# dcmotor.net
KiCad netlist of a schematic drawn in EAGLE
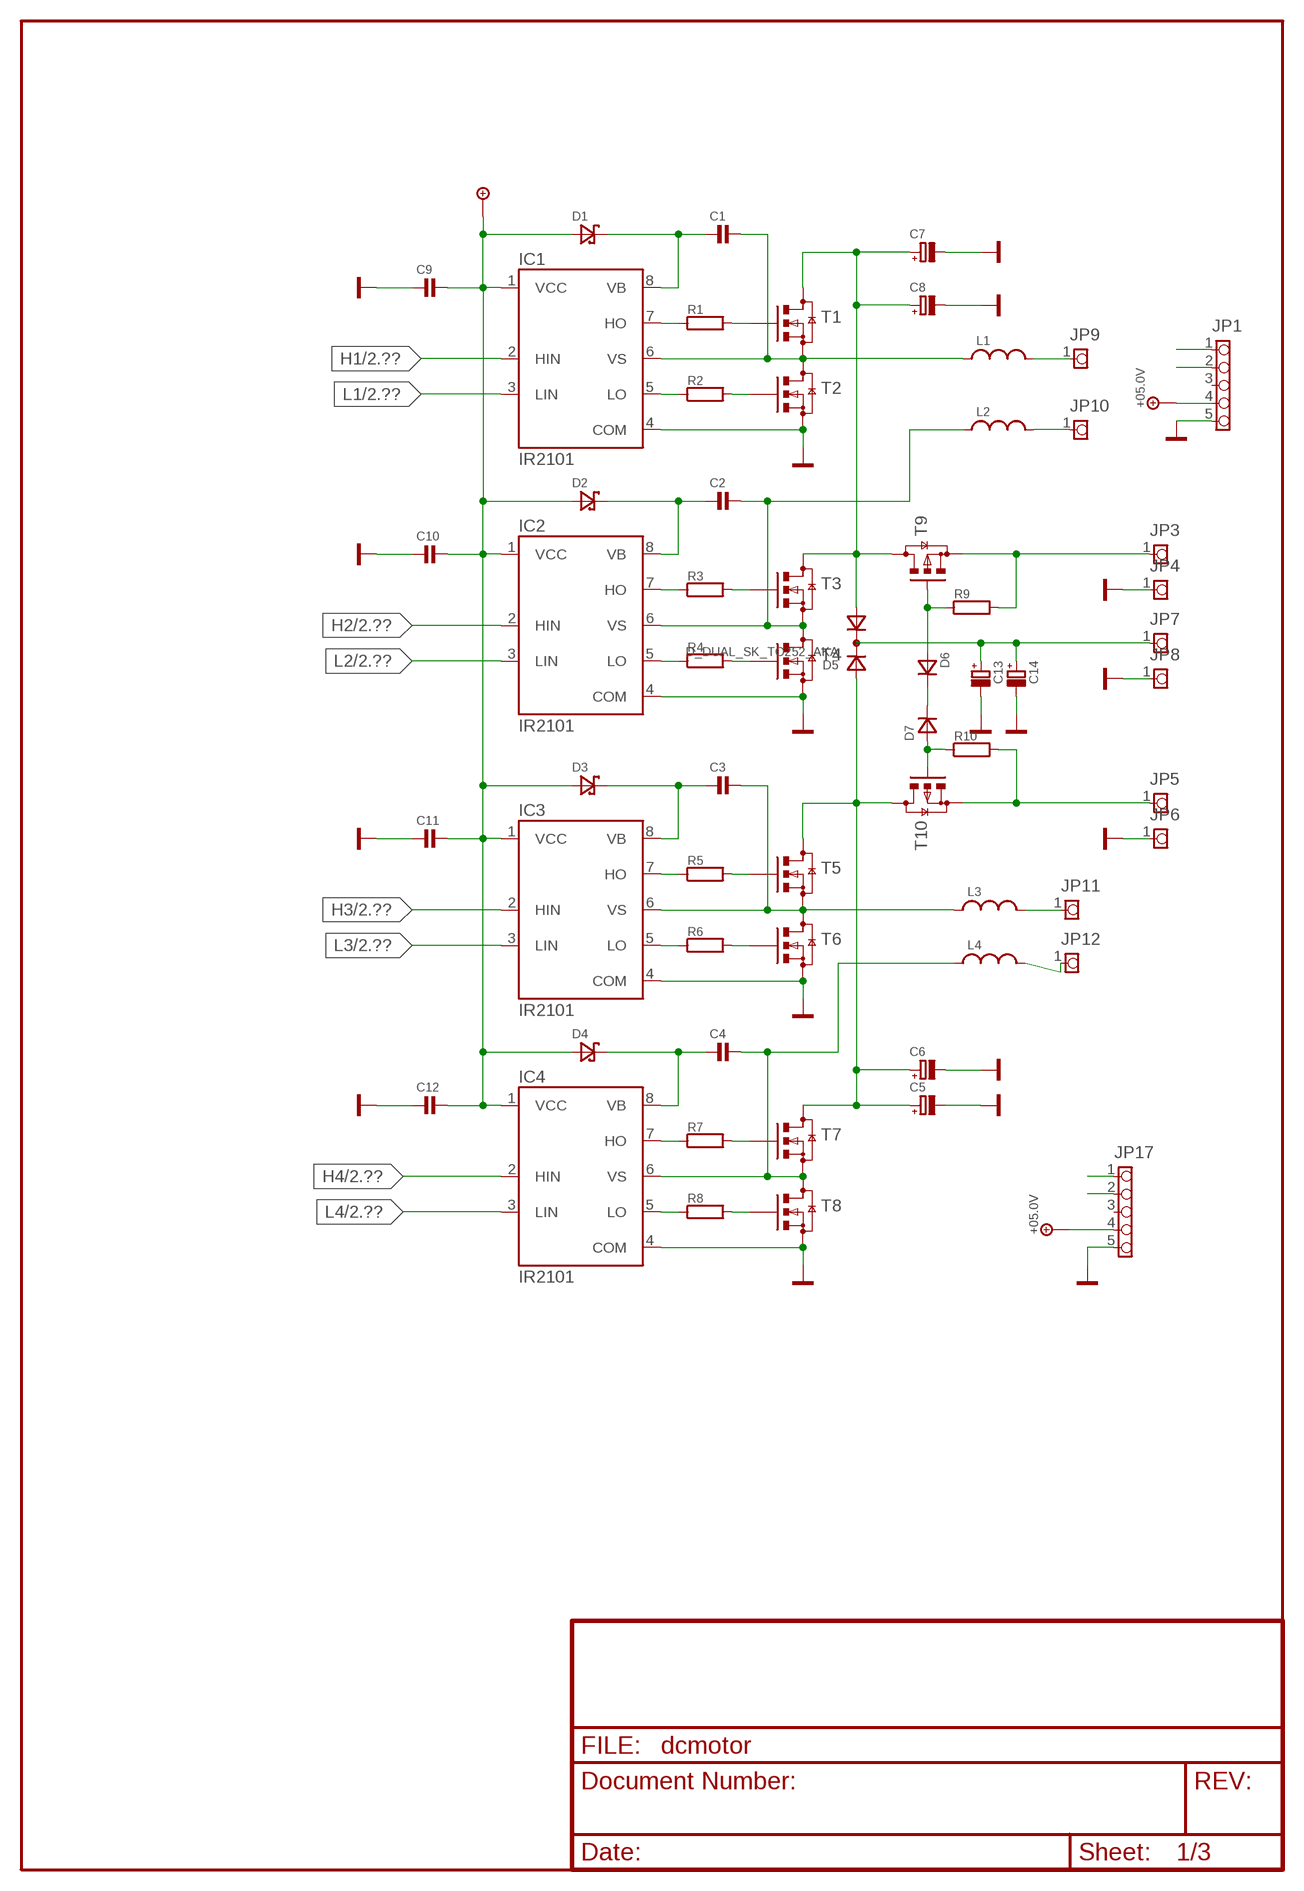
[diagram p0: schematic, sheet 1]
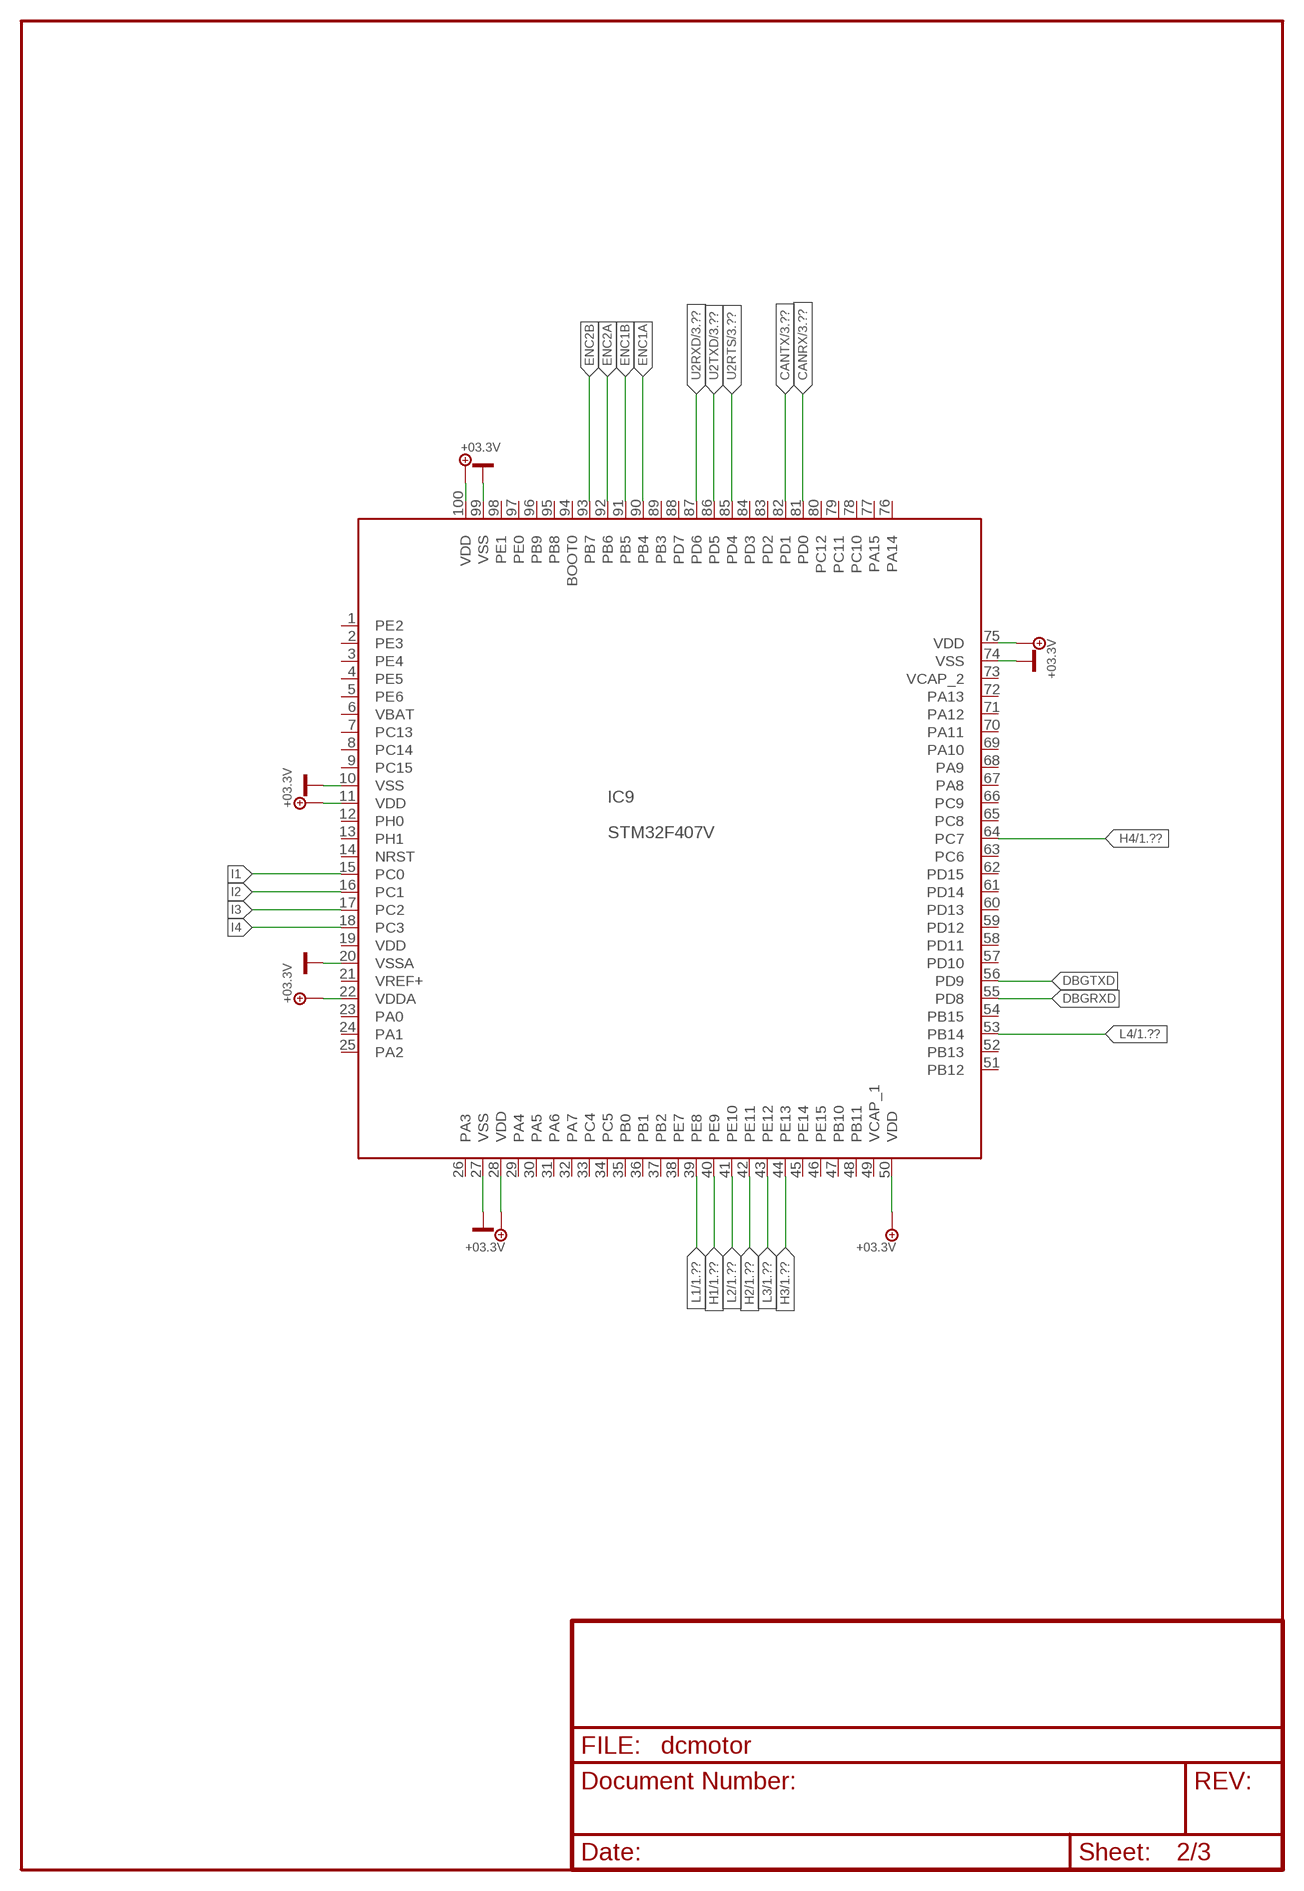
[diagram p1: schematic, sheet 2]
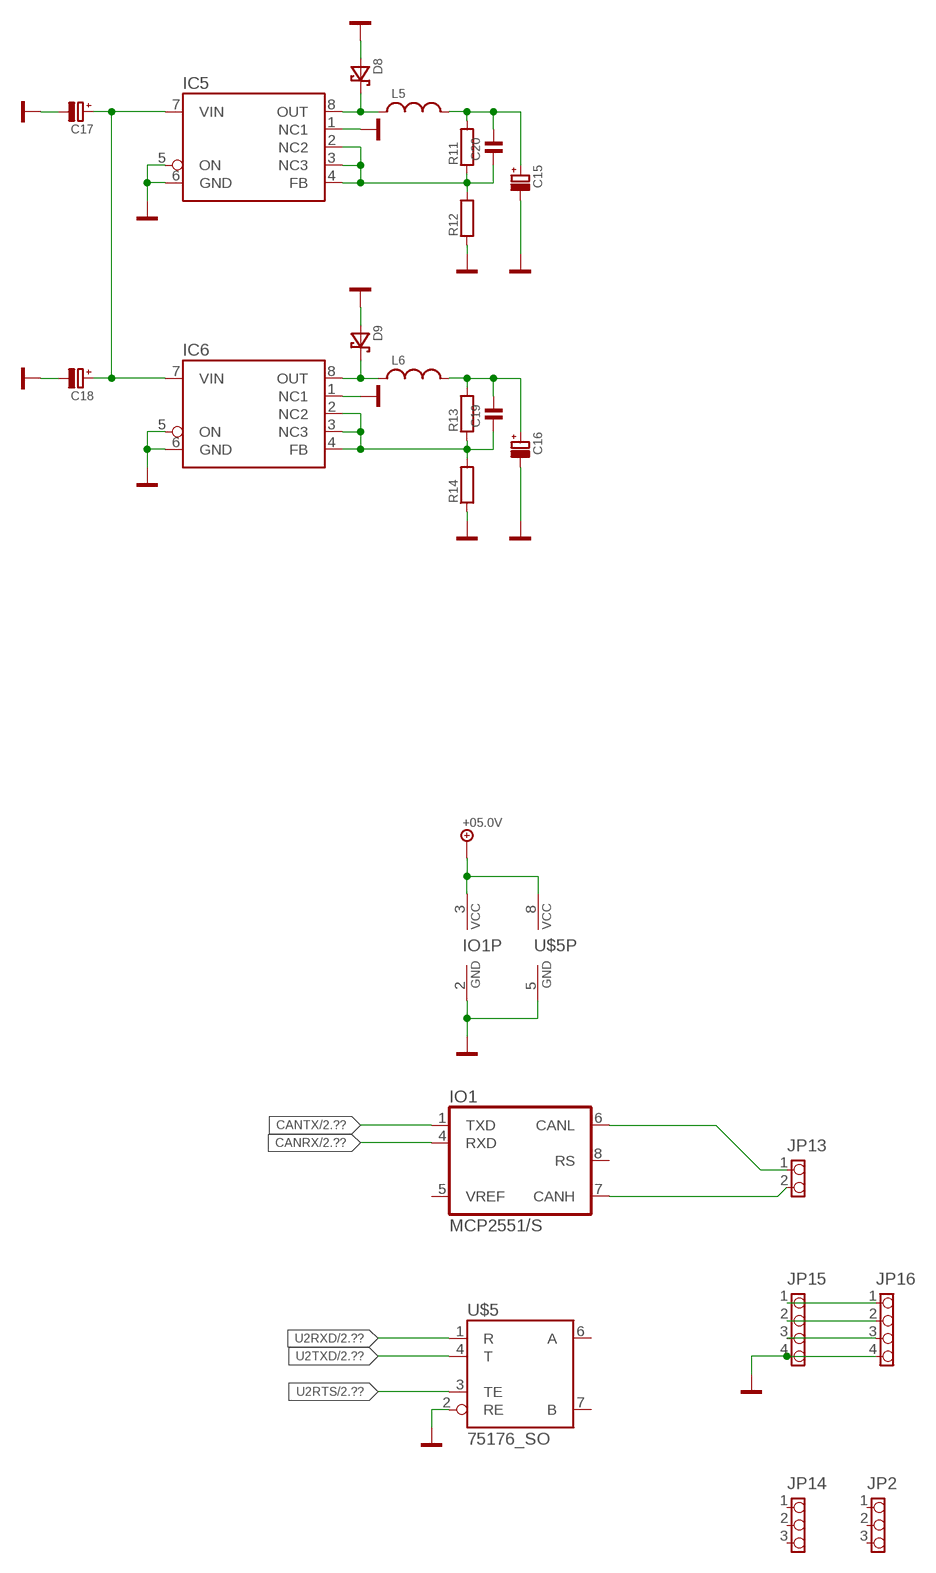
[diagram p2: schematic, sheet 3]

(export (version "E")
  (design (tool "Eeschema 10.0.6"))
  (components
    (comp (ref "C1")
      (value "C1206")
      (footprint "eagle-import:1206")
      (libsource (lib "eagle-import") (part "C1206"))
    )
    (comp (ref "C2")
      (value "C1206")
      (footprint "eagle-import:1206")
      (libsource (lib "eagle-import") (part "C1206"))
    )
    (comp (ref "C3")
      (value "C1206")
      (footprint "eagle-import:1206")
      (libsource (lib "eagle-import") (part "C1206"))
    )
    (comp (ref "C4")
      (value "C1206")
      (footprint "eagle-import:1206")
      (libsource (lib "eagle-import") (part "C1206"))
    )
    (comp (ref "C5")
      (value "CECT7343")
      (footprint "eagle-import:CT7343D")
      (libsource (lib "eagle-import") (part "CECT7343"))
    )
    (comp (ref "C6")
      (value "CECT7343")
      (footprint "eagle-import:CT7343D")
      (libsource (lib "eagle-import") (part "CECT7343"))
    )
    (comp (ref "C7")
      (value "CECT7343")
      (footprint "eagle-import:CT7343D")
      (libsource (lib "eagle-import") (part "CECT7343"))
    )
    (comp (ref "C8")
      (value "CECT7343")
      (footprint "eagle-import:CT7343D")
      (libsource (lib "eagle-import") (part "CECT7343"))
    )
    (comp (ref "C9")
      (value "C1206")
      (footprint "eagle-import:1206")
      (libsource (lib "eagle-import") (part "C1206"))
    )
    (comp (ref "C10")
      (value "C1206")
      (footprint "eagle-import:1206")
      (libsource (lib "eagle-import") (part "C1206"))
    )
    (comp (ref "C11")
      (value "C1206")
      (footprint "eagle-import:1206")
      (libsource (lib "eagle-import") (part "C1206"))
    )
    (comp (ref "C12")
      (value "C1206")
      (footprint "eagle-import:1206")
      (libsource (lib "eagle-import") (part "C1206"))
    )
    (comp (ref "C13")
      (value "CECT7343")
      (footprint "eagle-import:CT7343D")
      (libsource (lib "eagle-import") (part "CECT7343"))
    )
    (comp (ref "C14")
      (value "CECT7343")
      (footprint "eagle-import:CT7343D")
      (libsource (lib "eagle-import") (part "CECT7343"))
    )
    (comp (ref "D1")
      (value "D_SCHOTKY_MLL34")
      (footprint "eagle-import:D_MLL34")
      (libsource (lib "eagle-import") (part "D_SCHOTKY_MLL34"))
    )
    (comp (ref "D2")
      (value "D_SCHOTKY_MLL34")
      (footprint "eagle-import:D_MLL34")
      (libsource (lib "eagle-import") (part "D_SCHOTKY_MLL34"))
    )
    (comp (ref "D3")
      (value "D_SCHOTKY_MLL34")
      (footprint "eagle-import:D_MLL34")
      (libsource (lib "eagle-import") (part "D_SCHOTKY_MLL34"))
    )
    (comp (ref "D4")
      (value "D_SCHOTKY_MLL34")
      (footprint "eagle-import:D_MLL34")
      (libsource (lib "eagle-import") (part "D_SCHOTKY_MLL34"))
    )
    (comp (ref "D5")
      (value "D_DUAL_SK_TO252_AKA")
      (footprint "eagle-import:TO252")
      (libsource (lib "eagle-import") (part "D_DUAL_SK_TO252_AKA"))
    )
    (comp (ref "D6")
      (value "D_MLL34")
      (footprint "eagle-import:D_MLL34")
      (libsource (lib "eagle-import") (part "D_MLL34"))
    )
    (comp (ref "D7")
      (value "D_MLL34")
      (footprint "eagle-import:D_MLL34")
      (libsource (lib "eagle-import") (part "D_MLL34"))
    )
    (comp (ref "IC1")
      (value "IR2101")
      (footprint "eagle-import:SO08")
      (libsource (lib "eagle-import") (part "IR2101"))
    )
    (comp (ref "IC2")
      (value "IR2101")
      (footprint "eagle-import:SO08")
      (libsource (lib "eagle-import") (part "IR2101"))
    )
    (comp (ref "IC3")
      (value "IR2101")
      (footprint "eagle-import:SO08")
      (libsource (lib "eagle-import") (part "IR2101"))
    )
    (comp (ref "IC4")
      (value "IR2101")
      (footprint "eagle-import:SO08")
      (libsource (lib "eagle-import") (part "IR2101"))
    )
    (comp (ref "JP1")
      (value "PINHD-1X5_250_MX5267")
      (footprint "eagle-import:1X05_250_MX5267")
      (libsource (lib "eagle-import") (part "PINHD-1X5_250_MX5267"))
    )
    (comp (ref "JP3")
      (value "PINHD-1X1")
      (footprint "eagle-import:1X01_254")
      (libsource (lib "eagle-import") (part "PINHD-1X1"))
    )
    (comp (ref "JP4")
      (value "PINHD-1X1")
      (footprint "eagle-import:1X01_254")
      (libsource (lib "eagle-import") (part "PINHD-1X1"))
    )
    (comp (ref "JP5")
      (value "PINHD-1X1")
      (footprint "eagle-import:1X01_254")
      (libsource (lib "eagle-import") (part "PINHD-1X1"))
    )
    (comp (ref "JP6")
      (value "PINHD-1X1")
      (footprint "eagle-import:1X01_254")
      (libsource (lib "eagle-import") (part "PINHD-1X1"))
    )
    (comp (ref "JP7")
      (value "PINHD-1X1")
      (footprint "eagle-import:1X01_254")
      (libsource (lib "eagle-import") (part "PINHD-1X1"))
    )
    (comp (ref "JP8")
      (value "PINHD-1X1")
      (footprint "eagle-import:1X01_254")
      (libsource (lib "eagle-import") (part "PINHD-1X1"))
    )
    (comp (ref "JP9")
      (value "PINHD-1X1")
      (footprint "eagle-import:1X01_254")
      (libsource (lib "eagle-import") (part "PINHD-1X1"))
    )
    (comp (ref "JP10")
      (value "PINHD-1X1")
      (footprint "eagle-import:1X01_254")
      (libsource (lib "eagle-import") (part "PINHD-1X1"))
    )
    (comp (ref "JP11")
      (value "PINHD-1X1")
      (footprint "eagle-import:1X01_254")
      (libsource (lib "eagle-import") (part "PINHD-1X1"))
    )
    (comp (ref "JP12")
      (value "PINHD-1X1")
      (footprint "eagle-import:1X01_254")
      (libsource (lib "eagle-import") (part "PINHD-1X1"))
    )
    (comp (ref "JP17")
      (value "PINHD-1X5_250_MX5267")
      (footprint "eagle-import:1X05_250_MX5267")
      (libsource (lib "eagle-import") (part "PINHD-1X5_250_MX5267"))
    )
    (comp (ref "L1")
      (value "L_CDRH127")
      (footprint "eagle-import:L_CDRH127")
      (libsource (lib "eagle-import") (part "L_CDRH127"))
    )
    (comp (ref "L2")
      (value "L_CDRH127")
      (footprint "eagle-import:L_CDRH127")
      (libsource (lib "eagle-import") (part "L_CDRH127"))
    )
    (comp (ref "L3")
      (value "L_CDRH127")
      (footprint "eagle-import:L_CDRH127")
      (libsource (lib "eagle-import") (part "L_CDRH127"))
    )
    (comp (ref "L4")
      (value "L_CDRH127")
      (footprint "eagle-import:L_CDRH127")
      (libsource (lib "eagle-import") (part "L_CDRH127"))
    )
    (comp (ref "R1")
      (value "R_R0603")
      (footprint "eagle-import:0603")
      (libsource (lib "eagle-import") (part "R_R0603"))
    )
    (comp (ref "R2")
      (value "R_R0603")
      (footprint "eagle-import:0603")
      (libsource (lib "eagle-import") (part "R_R0603"))
    )
    (comp (ref "R3")
      (value "R_R0603")
      (footprint "eagle-import:0603")
      (libsource (lib "eagle-import") (part "R_R0603"))
    )
    (comp (ref "R4")
      (value "R_R0603")
      (footprint "eagle-import:0603")
      (libsource (lib "eagle-import") (part "R_R0603"))
    )
    (comp (ref "R5")
      (value "R_R0603")
      (footprint "eagle-import:0603")
      (libsource (lib "eagle-import") (part "R_R0603"))
    )
    (comp (ref "R6")
      (value "R_R0603")
      (footprint "eagle-import:0603")
      (libsource (lib "eagle-import") (part "R_R0603"))
    )
    (comp (ref "R7")
      (value "R_R0603")
      (footprint "eagle-import:0603")
      (libsource (lib "eagle-import") (part "R_R0603"))
    )
    (comp (ref "R8")
      (value "R_R0603")
      (footprint "eagle-import:0603")
      (libsource (lib "eagle-import") (part "R_R0603"))
    )
    (comp (ref "R9")
      (value "R_R0603")
      (footprint "eagle-import:0603")
      (libsource (lib "eagle-import") (part "R_R0603"))
    )
    (comp (ref "R10")
      (value "R_R0603")
      (footprint "eagle-import:0603")
      (libsource (lib "eagle-import") (part "R_R0603"))
    )
    (comp (ref "T1")
      (value "_EMOS_N_TO252_GDS")
      (footprint "eagle-import:TO252")
      (libsource (lib "eagle-import") (part "_EMOS_N_TO252_GDS"))
    )
    (comp (ref "T2")
      (value "_EMOS_N_TO252_GDS")
      (footprint "eagle-import:TO252")
      (libsource (lib "eagle-import") (part "_EMOS_N_TO252_GDS"))
    )
    (comp (ref "T3")
      (value "_EMOS_N_TO252_GDS")
      (footprint "eagle-import:TO252")
      (libsource (lib "eagle-import") (part "_EMOS_N_TO252_GDS"))
    )
    (comp (ref "T4")
      (value "_EMOS_N_TO252_GDS")
      (footprint "eagle-import:TO252")
      (libsource (lib "eagle-import") (part "_EMOS_N_TO252_GDS"))
    )
    (comp (ref "T5")
      (value "_EMOS_N_TO252_GDS")
      (footprint "eagle-import:TO252")
      (libsource (lib "eagle-import") (part "_EMOS_N_TO252_GDS"))
    )
    (comp (ref "T6")
      (value "_EMOS_N_TO252_GDS")
      (footprint "eagle-import:TO252")
      (libsource (lib "eagle-import") (part "_EMOS_N_TO252_GDS"))
    )
    (comp (ref "T7")
      (value "_EMOS_N_TO252_GDS")
      (footprint "eagle-import:TO252")
      (libsource (lib "eagle-import") (part "_EMOS_N_TO252_GDS"))
    )
    (comp (ref "T8")
      (value "_EMOS_N_TO252_GDS")
      (footprint "eagle-import:TO252")
      (libsource (lib "eagle-import") (part "_EMOS_N_TO252_GDS"))
    )
    (comp (ref "T9")
      (value "_EMOS_P_TO252_GDS")
      (footprint "eagle-import:TO252")
      (libsource (lib "eagle-import") (part "_EMOS_P_TO252_GDS"))
    )
    (comp (ref "T10")
      (value "_EMOS_P_TO252_GDS")
      (footprint "eagle-import:TO252")
      (libsource (lib "eagle-import") (part "_EMOS_P_TO252_GDS"))
    )
    (comp (ref "IC9")
      (value "STM32F407V")
      (footprint "eagle-import:LQFP100")
      (libsource (lib "eagle-import") (part "STM32F4V07"))
    )
    (comp (ref "C15")
      (value "CECT7343")
      (footprint "eagle-import:CT7343D")
      (libsource (lib "eagle-import") (part "CECT7343"))
    )
    (comp (ref "C16")
      (value "CECT7343")
      (footprint "eagle-import:CT7343D")
      (libsource (lib "eagle-import") (part "CECT7343"))
    )
    (comp (ref "C17")
      (value "CECT7343")
      (footprint "eagle-import:CT7343D")
      (libsource (lib "eagle-import") (part "CECT7343"))
    )
    (comp (ref "C18")
      (value "CECT7343")
      (footprint "eagle-import:CT7343D")
      (libsource (lib "eagle-import") (part "CECT7343"))
    )
    (comp (ref "C19")
      (value "C0603")
      (footprint "eagle-import:0603")
      (libsource (lib "eagle-import") (part "C0603"))
    )
    (comp (ref "C20")
      (value "C0603")
      (footprint "eagle-import:0603")
      (libsource (lib "eagle-import") (part "C0603"))
    )
    (comp (ref "D8")
      (value "D_SCHOTKY_SMB")
      (footprint "eagle-import:D_SMB")
      (libsource (lib "eagle-import") (part "D_SCHOTKY_SMB"))
    )
    (comp (ref "D9")
      (value "D_SCHOTKY_SMB")
      (footprint "eagle-import:D_SMB")
      (libsource (lib "eagle-import") (part "D_SCHOTKY_SMB"))
    )
    (comp (ref "IC5")
      (value "LM2594_SO")
      (footprint "eagle-import:SO08")
      (libsource (lib "eagle-import") (part "LM2594_SO"))
    )
    (comp (ref "IC6")
      (value "LM2594_SO")
      (footprint "eagle-import:SO08")
      (libsource (lib "eagle-import") (part "LM2594_SO"))
    )
    (comp (ref "IO1")
      (value "MCP2551/S")
      (footprint "eagle-import:SO08")
      (libsource (lib "eagle-import") (part "MCP2551/S"))
    )
    (comp (ref "JP2")
      (value "PINHD-1X3_250_MX5267")
      (footprint "eagle-import:1X03_250_MX5267")
      (libsource (lib "eagle-import") (part "PINHD-1X3_250_MX5267"))
    )
    (comp (ref "JP13")
      (value "PINHD-1X2_250_MX5267")
      (footprint "eagle-import:1X02_250_MX5267")
      (libsource (lib "eagle-import") (part "PINHD-1X2_250_MX5267"))
    )
    (comp (ref "JP14")
      (value "PINHD-1X3_250_MX5267")
      (footprint "eagle-import:1X03_250_MX5267")
      (libsource (lib "eagle-import") (part "PINHD-1X3_250_MX5267"))
    )
    (comp (ref "JP15")
      (value "PINHD-1X4_250_MX5267")
      (footprint "eagle-import:1X04_250_MX5267")
      (libsource (lib "eagle-import") (part "PINHD-1X4_250_MX5267"))
    )
    (comp (ref "JP16")
      (value "PINHD-1X4_250_MX5267")
      (footprint "eagle-import:1X04_250_MX5267")
      (libsource (lib "eagle-import") (part "PINHD-1X4_250_MX5267"))
    )
    (comp (ref "L5")
      (value "L_SMD_350_200")
      (footprint "eagle-import:L_350_200")
      (libsource (lib "eagle-import") (part "L_SMD_350_200"))
    )
    (comp (ref "L6")
      (value "L_SMD_350_200")
      (footprint "eagle-import:L_350_200")
      (libsource (lib "eagle-import") (part "L_SMD_350_200"))
    )
    (comp (ref "R11")
      (value "R_R0603")
      (footprint "eagle-import:0603")
      (libsource (lib "eagle-import") (part "R_R0603"))
    )
    (comp (ref "R12")
      (value "R_R0603")
      (footprint "eagle-import:0603")
      (libsource (lib "eagle-import") (part "R_R0603"))
    )
    (comp (ref "R13")
      (value "R_R0603")
      (footprint "eagle-import:0603")
      (libsource (lib "eagle-import") (part "R_R0603"))
    )
    (comp (ref "R14")
      (value "R_R0603")
      (footprint "eagle-import:0603")
      (libsource (lib "eagle-import") (part "R_R0603"))
    )
    (comp (ref "U$5")
      (value "75176_SO")
      (footprint "eagle-import:SO08")
      (libsource (lib "eagle-import") (part "75176_SO"))
    )
  )
  (nets
    (net (code "1") (name "+3.3V") (class "Default")
      (node (ref "IC9") (pin "100") (pinfunction "VDD_100") (pintype "passive"))
      (node (ref "IC9") (pin "11") (pinfunction "VDD_11") (pintype "passive"))
      (node (ref "IC9") (pin "22") (pinfunction "VDDA_22") (pintype "passive"))
      (node (ref "IC9") (pin "28") (pinfunction "VDD_28") (pintype "passive"))
      (node (ref "IC9") (pin "50") (pinfunction "VDD_50") (pintype "passive"))
      (node (ref "IC9") (pin "75") (pinfunction "VDD_75") (pintype "passive"))
    )
    (net (code "2") (name "+5.0V") (class "Default")
      (node (ref "IO1") (pin "3") (pinfunction "VCC_3") (pintype "power_in"))
      (node (ref "JP1") (pin "4") (pinfunction "4_4") (pintype "passive"))
      (node (ref "JP17") (pin "4") (pinfunction "4_4") (pintype "passive"))
      (node (ref "U$5") (pin "8") (pinfunction "VCC_8") (pintype "power_in"))
    )
    (net (code "3") (name "+15V") (class "Default")
      (node (ref "C10") (pin "1") (pinfunction "1_1") (pintype "passive"))
      (node (ref "C11") (pin "1") (pinfunction "1_1") (pintype "passive"))
      (node (ref "C12") (pin "1") (pinfunction "1_1") (pintype "passive"))
      (node (ref "C9") (pin "1") (pinfunction "1_1") (pintype "passive"))
      (node (ref "D1") (pin "A") (pinfunction "A_A") (pintype "passive"))
      (node (ref "D2") (pin "A") (pinfunction "A_A") (pintype "passive"))
      (node (ref "D3") (pin "A") (pinfunction "A_A") (pintype "passive"))
      (node (ref "D4") (pin "A") (pinfunction "A_A") (pintype "passive"))
      (node (ref "IC1") (pin "1") (pinfunction "VCC_1") (pintype "passive"))
      (node (ref "IC2") (pin "1") (pinfunction "VCC_1") (pintype "passive"))
      (node (ref "IC3") (pin "1") (pinfunction "VCC_1") (pintype "passive"))
      (node (ref "IC4") (pin "1") (pinfunction "VCC_1") (pintype "passive"))
    )
    (net (code "4") (name "CANRX") (class "Default")
      (node (ref "IC9") (pin "81") (pinfunction "PD0_81") (pintype "passive"))
      (node (ref "IO1") (pin "4") (pinfunction "RXD_4") (pintype "output"))
    )
    (net (code "5") (name "CANTX") (class "Default")
      (node (ref "IC9") (pin "82") (pinfunction "PD1_82") (pintype "passive"))
      (node (ref "IO1") (pin "1") (pinfunction "TXD_1") (pintype "input"))
    )
    (net (code "6") (name "DBGRXD") (class "Default")
      (node (ref "IC9") (pin "55") (pinfunction "PD8_55") (pintype "passive"))
    )
    (net (code "7") (name "DBGTXD") (class "Default")
      (node (ref "IC9") (pin "56") (pinfunction "PD9_56") (pintype "passive"))
    )
    (net (code "8") (name "ENC1A") (class "Default")
      (node (ref "IC9") (pin "90") (pinfunction "PB4_90") (pintype "passive"))
      (node (ref "JP1") (pin "1") (pinfunction "1_1") (pintype "passive"))
    )
    (net (code "9") (name "ENC1B") (class "Default")
      (node (ref "IC9") (pin "91") (pinfunction "PB5_91") (pintype "passive"))
      (node (ref "JP1") (pin "2") (pinfunction "2_2") (pintype "passive"))
    )
    (net (code "10") (name "ENC2A") (class "Default")
      (node (ref "IC9") (pin "92") (pinfunction "PB6_92") (pintype "passive"))
      (node (ref "JP17") (pin "1") (pinfunction "1_1") (pintype "passive"))
    )
    (net (code "11") (name "ENC2B") (class "Default")
      (node (ref "IC9") (pin "93") (pinfunction "PB7_93") (pintype "passive"))
      (node (ref "JP17") (pin "2") (pinfunction "2_2") (pintype "passive"))
    )
    (net (code "12") (name "GND") (class "Default")
      (node (ref "C10") (pin "2") (pinfunction "2_2") (pintype "passive"))
      (node (ref "C11") (pin "2") (pinfunction "2_2") (pintype "passive"))
      (node (ref "C12") (pin "2") (pinfunction "2_2") (pintype "passive"))
      (node (ref "C13") (pin "-") (pinfunction "-_-") (pintype "passive"))
      (node (ref "C14") (pin "-") (pinfunction "-_-") (pintype "passive"))
      (node (ref "C15") (pin "-") (pinfunction "-_-") (pintype "passive"))
      (node (ref "C16") (pin "-") (pinfunction "-_-") (pintype "passive"))
      (node (ref "C17") (pin "-") (pinfunction "-_-") (pintype "passive"))
      (node (ref "C18") (pin "-") (pinfunction "-_-") (pintype "passive"))
      (node (ref "C5") (pin "-") (pinfunction "-_-") (pintype "passive"))
      (node (ref "C6") (pin "-") (pinfunction "-_-") (pintype "passive"))
      (node (ref "C7") (pin "-") (pinfunction "-_-") (pintype "passive"))
      (node (ref "C8") (pin "-") (pinfunction "-_-") (pintype "passive"))
      (node (ref "C9") (pin "2") (pinfunction "2_2") (pintype "passive"))
      (node (ref "D8") (pin "A") (pinfunction "A_A") (pintype "passive"))
      (node (ref "D9") (pin "A") (pinfunction "A_A") (pintype "passive"))
      (node (ref "IC1") (pin "4") (pinfunction "COM_4") (pintype "passive"))
      (node (ref "IC2") (pin "4") (pinfunction "COM_4") (pintype "passive"))
      (node (ref "IC3") (pin "4") (pinfunction "COM_4") (pintype "passive"))
      (node (ref "IC4") (pin "4") (pinfunction "COM_4") (pintype "passive"))
      (node (ref "IC5") (pin "1") (pinfunction "NC1_1") (pintype "passive"))
      (node (ref "IC5") (pin "5") (pinfunction "ON_5") (pintype "passive"))
      (node (ref "IC5") (pin "6") (pinfunction "GND_6") (pintype "passive"))
      (node (ref "IC6") (pin "1") (pinfunction "NC1_1") (pintype "passive"))
      (node (ref "IC6") (pin "5") (pinfunction "ON_5") (pintype "passive"))
      (node (ref "IC6") (pin "6") (pinfunction "GND_6") (pintype "passive"))
      (node (ref "IC9") (pin "10") (pinfunction "VSS_10") (pintype "passive"))
      (node (ref "IC9") (pin "20") (pinfunction "VSSA_20") (pintype "passive"))
      (node (ref "IC9") (pin "27") (pinfunction "VSS_27") (pintype "passive"))
      (node (ref "IC9") (pin "74") (pinfunction "VSS_74") (pintype "passive"))
      (node (ref "IC9") (pin "99") (pinfunction "VSS_99") (pintype "passive"))
      (node (ref "IO1") (pin "2") (pinfunction "GND_2") (pintype "power_in"))
      (node (ref "JP1") (pin "5") (pinfunction "5_5") (pintype "passive"))
      (node (ref "JP15") (pin "4") (pinfunction "4_4") (pintype "passive"))
      (node (ref "JP16") (pin "4") (pinfunction "4_4") (pintype "passive"))
      (node (ref "JP17") (pin "5") (pinfunction "5_5") (pintype "passive"))
      (node (ref "JP4") (pin "1") (pinfunction "1_1") (pintype "passive"))
      (node (ref "JP6") (pin "1") (pinfunction "1_1") (pintype "passive"))
      (node (ref "JP8") (pin "1") (pinfunction "1_1") (pintype "passive"))
      (node (ref "R12") (pin "1") (pinfunction "1_1") (pintype "passive"))
      (node (ref "R14") (pin "1") (pinfunction "1_1") (pintype "passive"))
      (node (ref "T2") (pin "3") (pinfunction "S_3") (pintype "passive"))
      (node (ref "T4") (pin "3") (pinfunction "S_3") (pintype "passive"))
      (node (ref "T6") (pin "3") (pinfunction "S_3") (pintype "passive"))
      (node (ref "T8") (pin "3") (pinfunction "S_3") (pintype "passive"))
      (node (ref "U$5") (pin "2") (pinfunction "RE_2") (pintype "input"))
      (node (ref "U$5") (pin "5") (pinfunction "GND_5") (pintype "power_in"))
    )
    (net (code "13") (name "H1") (class "Default")
      (node (ref "IC1") (pin "2") (pinfunction "HIN_2") (pintype "passive"))
      (node (ref "IC9") (pin "40") (pinfunction "PE9_40") (pintype "passive"))
    )
    (net (code "14") (name "H2") (class "Default")
      (node (ref "IC2") (pin "2") (pinfunction "HIN_2") (pintype "passive"))
      (node (ref "IC9") (pin "42") (pinfunction "PE11_42") (pintype "passive"))
    )
    (net (code "15") (name "H3") (class "Default")
      (node (ref "IC3") (pin "2") (pinfunction "HIN_2") (pintype "passive"))
      (node (ref "IC9") (pin "44") (pinfunction "PE13_44") (pintype "passive"))
    )
    (net (code "16") (name "H4") (class "Default")
      (node (ref "IC4") (pin "2") (pinfunction "HIN_2") (pintype "passive"))
      (node (ref "IC9") (pin "64") (pinfunction "PC7_64") (pintype "passive"))
    )
    (net (code "17") (name "I1") (class "Default")
      (node (ref "IC9") (pin "15") (pinfunction "PC0_15") (pintype "passive"))
    )
    (net (code "18") (name "I2") (class "Default")
      (node (ref "IC9") (pin "16") (pinfunction "PC1_16") (pintype "passive"))
    )
    (net (code "19") (name "I3") (class "Default")
      (node (ref "IC9") (pin "17") (pinfunction "PC2_17") (pintype "passive"))
    )
    (net (code "20") (name "I4") (class "Default")
      (node (ref "IC9") (pin "18") (pinfunction "PC3_18") (pintype "passive"))
    )
    (net (code "21") (name "L1") (class "Default")
      (node (ref "IC1") (pin "3") (pinfunction "LIN_3") (pintype "passive"))
      (node (ref "IC9") (pin "39") (pinfunction "PE8_39") (pintype "passive"))
    )
    (net (code "22") (name "L2") (class "Default")
      (node (ref "IC2") (pin "3") (pinfunction "LIN_3") (pintype "passive"))
      (node (ref "IC9") (pin "41") (pinfunction "PE10_41") (pintype "passive"))
    )
    (net (code "23") (name "L3") (class "Default")
      (node (ref "IC3") (pin "3") (pinfunction "LIN_3") (pintype "passive"))
      (node (ref "IC9") (pin "43") (pinfunction "PE12_43") (pintype "passive"))
    )
    (net (code "24") (name "L4") (class "Default")
      (node (ref "IC4") (pin "3") (pinfunction "LIN_3") (pintype "passive"))
      (node (ref "IC9") (pin "53") (pinfunction "PB14_53") (pintype "passive"))
    )
    (net (code "25") (name "Net-(C15-Pad+)") (class "Default")
      (node (ref "C15") (pin "+") (pinfunction "+_+") (pintype "passive"))
      (node (ref "C20") (pin "1") (pinfunction "1_1") (pintype "passive"))
      (node (ref "L5") (pin "1") (pinfunction "1_1") (pintype "passive"))
      (node (ref "R11") (pin "2") (pinfunction "2_2") (pintype "passive"))
    )
    (net (code "26") (name "Net-(C16-Pad+)") (class "Default")
      (node (ref "C16") (pin "+") (pinfunction "+_+") (pintype "passive"))
      (node (ref "C19") (pin "1") (pinfunction "1_1") (pintype "passive"))
      (node (ref "L6") (pin "1") (pinfunction "1_1") (pintype "passive"))
      (node (ref "R13") (pin "2") (pinfunction "2_2") (pintype "passive"))
    )
    (net (code "27") (name "Net-(D5-A1)") (class "Default")
      (node (ref "C7") (pin "+") (pinfunction "+_+") (pintype "passive"))
      (node (ref "C8") (pin "+") (pinfunction "+_+") (pintype "passive"))
      (node (ref "D5") (pin "1") (pinfunction "A1_1") (pintype "passive"))
      (node (ref "T1") (pin "2") (pinfunction "D_2") (pintype "passive"))
      (node (ref "T3") (pin "2") (pinfunction "D_2") (pintype "passive"))
      (node (ref "T9") (pin "2") (pinfunction "D_2") (pintype "passive"))
    )
    (net (code "28") (name "Net-(D5-A2)") (class "Default")
      (node (ref "C5") (pin "+") (pinfunction "+_+") (pintype "passive"))
      (node (ref "C6") (pin "+") (pinfunction "+_+") (pintype "passive"))
      (node (ref "D5") (pin "3") (pinfunction "A2_3") (pintype "passive"))
      (node (ref "T10") (pin "2") (pinfunction "D_2") (pintype "passive"))
      (node (ref "T5") (pin "2") (pinfunction "D_2") (pintype "passive"))
      (node (ref "T7") (pin "2") (pinfunction "D_2") (pintype "passive"))
    )
    (net (code "29") (name "Net-(D5-K)") (class "Default")
      (node (ref "C13") (pin "+") (pinfunction "+_+") (pintype "passive"))
      (node (ref "C14") (pin "+") (pinfunction "+_+") (pintype "passive"))
      (node (ref "D5") (pin "2") (pinfunction "K_2") (pintype "passive"))
      (node (ref "JP7") (pin "1") (pinfunction "1_1") (pintype "passive"))
    )
    (net (code "30") (name "Net-(D6-PadK)") (class "Default")
      (node (ref "D6") (pin "K") (pinfunction "K_K") (pintype "passive"))
      (node (ref "D7") (pin "K") (pinfunction "K_K") (pintype "passive"))
    )
    (net (code "31") (name "Net-(IC1-HO)") (class "Default")
      (node (ref "IC1") (pin "7") (pinfunction "HO_7") (pintype "passive"))
      (node (ref "R1") (pin "1") (pinfunction "1_1") (pintype "passive"))
    )
    (net (code "32") (name "Net-(IC1-LO)") (class "Default")
      (node (ref "IC1") (pin "5") (pinfunction "LO_5") (pintype "passive"))
      (node (ref "R2") (pin "1") (pinfunction "1_1") (pintype "passive"))
    )
    (net (code "33") (name "Net-(IC1-VB)") (class "Default")
      (node (ref "C1") (pin "2") (pinfunction "2_2") (pintype "passive"))
      (node (ref "D1") (pin "K") (pinfunction "K_K") (pintype "passive"))
      (node (ref "IC1") (pin "8") (pinfunction "VB_8") (pintype "passive"))
    )
    (net (code "34") (name "Net-(IC1-VS)") (class "Default")
      (node (ref "C1") (pin "1") (pinfunction "1_1") (pintype "passive"))
      (node (ref "IC1") (pin "6") (pinfunction "VS_6") (pintype "passive"))
      (node (ref "L1") (pin "2") (pinfunction "2_2") (pintype "passive"))
      (node (ref "T1") (pin "3") (pinfunction "S_3") (pintype "passive"))
      (node (ref "T2") (pin "2") (pinfunction "D_2") (pintype "passive"))
    )
    (net (code "35") (name "Net-(IC2-HO)") (class "Default")
      (node (ref "IC2") (pin "7") (pinfunction "HO_7") (pintype "passive"))
      (node (ref "R3") (pin "1") (pinfunction "1_1") (pintype "passive"))
    )
    (net (code "36") (name "Net-(IC2-LO)") (class "Default")
      (node (ref "IC2") (pin "5") (pinfunction "LO_5") (pintype "passive"))
      (node (ref "R4") (pin "1") (pinfunction "1_1") (pintype "passive"))
    )
    (net (code "37") (name "Net-(IC2-VB)") (class "Default")
      (node (ref "C2") (pin "2") (pinfunction "2_2") (pintype "passive"))
      (node (ref "D2") (pin "K") (pinfunction "K_K") (pintype "passive"))
      (node (ref "IC2") (pin "8") (pinfunction "VB_8") (pintype "passive"))
    )
    (net (code "38") (name "Net-(IC2-VS)") (class "Default")
      (node (ref "C2") (pin "1") (pinfunction "1_1") (pintype "passive"))
      (node (ref "IC2") (pin "6") (pinfunction "VS_6") (pintype "passive"))
      (node (ref "L2") (pin "2") (pinfunction "2_2") (pintype "passive"))
      (node (ref "T3") (pin "3") (pinfunction "S_3") (pintype "passive"))
      (node (ref "T4") (pin "2") (pinfunction "D_2") (pintype "passive"))
    )
    (net (code "39") (name "Net-(IC3-HO)") (class "Default")
      (node (ref "IC3") (pin "7") (pinfunction "HO_7") (pintype "passive"))
      (node (ref "R5") (pin "1") (pinfunction "1_1") (pintype "passive"))
    )
    (net (code "40") (name "Net-(IC3-LO)") (class "Default")
      (node (ref "IC3") (pin "5") (pinfunction "LO_5") (pintype "passive"))
      (node (ref "R6") (pin "1") (pinfunction "1_1") (pintype "passive"))
    )
    (net (code "41") (name "Net-(IC3-VB)") (class "Default")
      (node (ref "C3") (pin "2") (pinfunction "2_2") (pintype "passive"))
      (node (ref "D3") (pin "K") (pinfunction "K_K") (pintype "passive"))
      (node (ref "IC3") (pin "8") (pinfunction "VB_8") (pintype "passive"))
    )
    (net (code "42") (name "Net-(IC3-VS)") (class "Default")
      (node (ref "C3") (pin "1") (pinfunction "1_1") (pintype "passive"))
      (node (ref "IC3") (pin "6") (pinfunction "VS_6") (pintype "passive"))
      (node (ref "L3") (pin "2") (pinfunction "2_2") (pintype "passive"))
      (node (ref "T5") (pin "3") (pinfunction "S_3") (pintype "passive"))
      (node (ref "T6") (pin "2") (pinfunction "D_2") (pintype "passive"))
    )
    (net (code "43") (name "Net-(IC4-HO)") (class "Default")
      (node (ref "IC4") (pin "7") (pinfunction "HO_7") (pintype "passive"))
      (node (ref "R7") (pin "1") (pinfunction "1_1") (pintype "passive"))
    )
    (net (code "44") (name "Net-(IC4-LO)") (class "Default")
      (node (ref "IC4") (pin "5") (pinfunction "LO_5") (pintype "passive"))
      (node (ref "R8") (pin "1") (pinfunction "1_1") (pintype "passive"))
    )
    (net (code "45") (name "Net-(IC4-VB)") (class "Default")
      (node (ref "C4") (pin "2") (pinfunction "2_2") (pintype "passive"))
      (node (ref "D4") (pin "K") (pinfunction "K_K") (pintype "passive"))
      (node (ref "IC4") (pin "8") (pinfunction "VB_8") (pintype "passive"))
    )
    (net (code "46") (name "Net-(IC4-VS)") (class "Default")
      (node (ref "C4") (pin "1") (pinfunction "1_1") (pintype "passive"))
      (node (ref "IC4") (pin "6") (pinfunction "VS_6") (pintype "passive"))
      (node (ref "L4") (pin "2") (pinfunction "2_2") (pintype "passive"))
      (node (ref "T7") (pin "3") (pinfunction "S_3") (pintype "passive"))
      (node (ref "T8") (pin "2") (pinfunction "D_2") (pintype "passive"))
    )
    (net (code "47") (name "Net-(IC5-FB)") (class "Default")
      (node (ref "C20") (pin "2") (pinfunction "2_2") (pintype "passive"))
      (node (ref "IC5") (pin "2") (pinfunction "NC2_2") (pintype "passive"))
      (node (ref "IC5") (pin "3") (pinfunction "NC3_3") (pintype "passive"))
      (node (ref "IC5") (pin "4") (pinfunction "FB_4") (pintype "passive"))
      (node (ref "R11") (pin "1") (pinfunction "1_1") (pintype "passive"))
      (node (ref "R12") (pin "2") (pinfunction "2_2") (pintype "passive"))
    )
    (net (code "48") (name "Net-(IC5-OUT)") (class "Default")
      (node (ref "D8") (pin "K") (pinfunction "K_K") (pintype "passive"))
      (node (ref "IC5") (pin "8") (pinfunction "OUT_8") (pintype "passive"))
      (node (ref "L5") (pin "2") (pinfunction "2_2") (pintype "passive"))
    )
    (net (code "49") (name "Net-(IC5-VIN)") (class "Default")
      (node (ref "C17") (pin "+") (pinfunction "+_+") (pintype "passive"))
      (node (ref "C18") (pin "+") (pinfunction "+_+") (pintype "passive"))
      (node (ref "IC5") (pin "7") (pinfunction "VIN_7") (pintype "passive"))
      (node (ref "IC6") (pin "7") (pinfunction "VIN_7") (pintype "passive"))
    )
    (net (code "50") (name "Net-(IC6-FB)") (class "Default")
      (node (ref "C19") (pin "2") (pinfunction "2_2") (pintype "passive"))
      (node (ref "IC6") (pin "2") (pinfunction "NC2_2") (pintype "passive"))
      (node (ref "IC6") (pin "3") (pinfunction "NC3_3") (pintype "passive"))
      (node (ref "IC6") (pin "4") (pinfunction "FB_4") (pintype "passive"))
      (node (ref "R13") (pin "1") (pinfunction "1_1") (pintype "passive"))
      (node (ref "R14") (pin "2") (pinfunction "2_2") (pintype "passive"))
    )
    (net (code "51") (name "Net-(IC6-OUT)") (class "Default")
      (node (ref "D9") (pin "K") (pinfunction "K_K") (pintype "passive"))
      (node (ref "IC6") (pin "8") (pinfunction "OUT_8") (pintype "passive"))
      (node (ref "L6") (pin "2") (pinfunction "2_2") (pintype "passive"))
    )
    (net (code "52") (name "Net-(IO1A-CANH)") (class "Default")
      (node (ref "IO1") (pin "7") (pinfunction "CANH_7") (pintype "bidirectional"))
      (node (ref "JP13") (pin "2") (pinfunction "2_2") (pintype "passive"))
    )
    (net (code "53") (name "Net-(IO1A-CANL)") (class "Default")
      (node (ref "IO1") (pin "6") (pinfunction "CANL_6") (pintype "bidirectional"))
      (node (ref "JP13") (pin "1") (pinfunction "1_1") (pintype "passive"))
    )
    (net (code "54") (name "Net-(JP9-Pad1)") (class "Default")
      (node (ref "JP9") (pin "1") (pinfunction "1_1") (pintype "passive"))
      (node (ref "L1") (pin "1") (pinfunction "1_1") (pintype "passive"))
    )
    (net (code "55") (name "Net-(JP10-Pad1)") (class "Default")
      (node (ref "JP10") (pin "1") (pinfunction "1_1") (pintype "passive"))
      (node (ref "L2") (pin "1") (pinfunction "1_1") (pintype "passive"))
    )
    (net (code "56") (name "Net-(JP11-Pad1)") (class "Default")
      (node (ref "JP11") (pin "1") (pinfunction "1_1") (pintype "passive"))
      (node (ref "L3") (pin "1") (pinfunction "1_1") (pintype "passive"))
    )
    (net (code "57") (name "Net-(JP12-Pad1)") (class "Default")
      (node (ref "JP12") (pin "1") (pinfunction "1_1") (pintype "passive"))
      (node (ref "L4") (pin "1") (pinfunction "1_1") (pintype "passive"))
    )
    (net (code "58") (name "Net-(JP15-Pad1)") (class "Default")
      (node (ref "JP15") (pin "1") (pinfunction "1_1") (pintype "passive"))
      (node (ref "JP16") (pin "1") (pinfunction "1_1") (pintype "passive"))
    )
    (net (code "59") (name "Net-(JP15-Pad2)") (class "Default")
      (node (ref "JP15") (pin "2") (pinfunction "2_2") (pintype "passive"))
      (node (ref "JP16") (pin "2") (pinfunction "2_2") (pintype "passive"))
    )
    (net (code "60") (name "Net-(JP15-Pad3)") (class "Default")
      (node (ref "JP15") (pin "3") (pinfunction "3_3") (pintype "passive"))
      (node (ref "JP16") (pin "3") (pinfunction "3_3") (pintype "passive"))
    )
    (net (code "61") (name "Net-(T1-G)") (class "Default")
      (node (ref "R1") (pin "2") (pinfunction "2_2") (pintype "passive"))
      (node (ref "T1") (pin "1") (pinfunction "G_1") (pintype "passive"))
    )
    (net (code "62") (name "Net-(T2-G)") (class "Default")
      (node (ref "R2") (pin "2") (pinfunction "2_2") (pintype "passive"))
      (node (ref "T2") (pin "1") (pinfunction "G_1") (pintype "passive"))
    )
    (net (code "63") (name "Net-(T3-G)") (class "Default")
      (node (ref "R3") (pin "2") (pinfunction "2_2") (pintype "passive"))
      (node (ref "T3") (pin "1") (pinfunction "G_1") (pintype "passive"))
    )
    (net (code "64") (name "Net-(T4-G)") (class "Default")
      (node (ref "R4") (pin "2") (pinfunction "2_2") (pintype "passive"))
      (node (ref "T4") (pin "1") (pinfunction "G_1") (pintype "passive"))
    )
    (net (code "65") (name "Net-(T5-G)") (class "Default")
      (node (ref "R5") (pin "2") (pinfunction "2_2") (pintype "passive"))
      (node (ref "T5") (pin "1") (pinfunction "G_1") (pintype "passive"))
    )
    (net (code "66") (name "Net-(T6-G)") (class "Default")
      (node (ref "R6") (pin "2") (pinfunction "2_2") (pintype "passive"))
      (node (ref "T6") (pin "1") (pinfunction "G_1") (pintype "passive"))
    )
    (net (code "67") (name "Net-(T7-G)") (class "Default")
      (node (ref "R7") (pin "2") (pinfunction "2_2") (pintype "passive"))
      (node (ref "T7") (pin "1") (pinfunction "G_1") (pintype "passive"))
    )
    (net (code "68") (name "Net-(T8-G)") (class "Default")
      (node (ref "R8") (pin "2") (pinfunction "2_2") (pintype "passive"))
      (node (ref "T8") (pin "1") (pinfunction "G_1") (pintype "passive"))
    )
    (net (code "69") (name "Net-(T9-G)") (class "Default")
      (node (ref "D6") (pin "A") (pinfunction "A_A") (pintype "passive"))
      (node (ref "R9") (pin "1") (pinfunction "1_1") (pintype "passive"))
      (node (ref "T9") (pin "1") (pinfunction "G_1") (pintype "passive"))
    )
    (net (code "70") (name "Net-(T9-S)") (class "Default")
      (node (ref "JP3") (pin "1") (pinfunction "1_1") (pintype "passive"))
      (node (ref "R9") (pin "2") (pinfunction "2_2") (pintype "passive"))
      (node (ref "T9") (pin "3") (pinfunction "S_3") (pintype "passive"))
    )
    (net (code "71") (name "Net-(T10-G)") (class "Default")
      (node (ref "D7") (pin "A") (pinfunction "A_A") (pintype "passive"))
      (node (ref "R10") (pin "1") (pinfunction "1_1") (pintype "passive"))
      (node (ref "T10") (pin "1") (pinfunction "G_1") (pintype "passive"))
    )
    (net (code "72") (name "Net-(T10-S)") (class "Default")
      (node (ref "JP5") (pin "1") (pinfunction "1_1") (pintype "passive"))
      (node (ref "R10") (pin "2") (pinfunction "2_2") (pintype "passive"))
      (node (ref "T10") (pin "3") (pinfunction "S_3") (pintype "passive"))
    )
    (net (code "73") (name "U2RTS") (class "Default")
      (node (ref "IC9") (pin "85") (pinfunction "PD4_85") (pintype "passive"))
      (node (ref "U$5") (pin "3") (pinfunction "TE_3") (pintype "input"))
    )
    (net (code "74") (name "U2RXD") (class "Default")
      (node (ref "IC9") (pin "87") (pinfunction "PD6_87") (pintype "passive"))
      (node (ref "U$5") (pin "1") (pinfunction "R_1") (pintype "output"))
    )
    (net (code "75") (name "U2TXD") (class "Default")
      (node (ref "IC9") (pin "86") (pinfunction "PD5_86") (pintype "passive"))
      (node (ref "U$5") (pin "4") (pinfunction "T_4") (pintype "input"))
    )
    (net (code "76") (name "unconnected-(IC9-BOOT0-Pad94)") (class "Default")
      (node (ref "IC9") (pin "94") (pinfunction "BOOT0_94") (pintype "passive"))
    )
    (net (code "77") (name "unconnected-(IC9-NRST-Pad14)") (class "Default")
      (node (ref "IC9") (pin "14") (pinfunction "NRST_14") (pintype "passive"))
    )
    (net (code "78") (name "unconnected-(IC9-PA0-Pad23)") (class "Default")
      (node (ref "IC9") (pin "23") (pinfunction "PA0_23") (pintype "passive"))
    )
    (net (code "79") (name "unconnected-(IC9-PA1-Pad24)") (class "Default")
      (node (ref "IC9") (pin "24") (pinfunction "PA1_24") (pintype "passive"))
    )
    (net (code "80") (name "unconnected-(IC9-PA2-Pad25)") (class "Default")
      (node (ref "IC9") (pin "25") (pinfunction "PA2_25") (pintype "passive"))
    )
    (net (code "81") (name "unconnected-(IC9-PA3-Pad26)") (class "Default")
      (node (ref "IC9") (pin "26") (pinfunction "PA3_26") (pintype "passive"))
    )
    (net (code "82") (name "unconnected-(IC9-PA4-Pad29)") (class "Default")
      (node (ref "IC9") (pin "29") (pinfunction "PA4_29") (pintype "passive"))
    )
    (net (code "83") (name "unconnected-(IC9-PA5-Pad30)") (class "Default")
      (node (ref "IC9") (pin "30") (pinfunction "PA5_30") (pintype "passive"))
    )
    (net (code "84") (name "unconnected-(IC9-PA6-Pad31)") (class "Default")
      (node (ref "IC9") (pin "31") (pinfunction "PA6_31") (pintype "passive"))
    )
    (net (code "85") (name "unconnected-(IC9-PA7-Pad32)") (class "Default")
      (node (ref "IC9") (pin "32") (pinfunction "PA7_32") (pintype "passive"))
    )
    (net (code "86") (name "unconnected-(IC9-PA8-Pad67)") (class "Default")
      (node (ref "IC9") (pin "67") (pinfunction "PA8_67") (pintype "passive"))
    )
    (net (code "87") (name "unconnected-(IC9-PA9-Pad68)") (class "Default")
      (node (ref "IC9") (pin "68") (pinfunction "PA9_68") (pintype "passive"))
    )
    (net (code "88") (name "unconnected-(IC9-PA10-Pad69)") (class "Default")
      (node (ref "IC9") (pin "69") (pinfunction "PA10_69") (pintype "passive"))
    )
    (net (code "89") (name "unconnected-(IC9-PA11-Pad70)") (class "Default")
      (node (ref "IC9") (pin "70") (pinfunction "PA11_70") (pintype "passive"))
    )
    (net (code "90") (name "unconnected-(IC9-PA12-Pad71)") (class "Default")
      (node (ref "IC9") (pin "71") (pinfunction "PA12_71") (pintype "passive"))
    )
    (net (code "91") (name "unconnected-(IC9-PA13-Pad72)") (class "Default")
      (node (ref "IC9") (pin "72") (pinfunction "PA13_72") (pintype "passive"))
    )
    (net (code "92") (name "unconnected-(IC9-PA14-Pad76)") (class "Default")
      (node (ref "IC9") (pin "76") (pinfunction "PA14_76") (pintype "passive"))
    )
    (net (code "93") (name "unconnected-(IC9-PA15-Pad77)") (class "Default")
      (node (ref "IC9") (pin "77") (pinfunction "PA15_77") (pintype "passive"))
    )
    (net (code "94") (name "unconnected-(IC9-PB0-Pad35)") (class "Default")
      (node (ref "IC9") (pin "35") (pinfunction "PB0_35") (pintype "passive"))
    )
    (net (code "95") (name "unconnected-(IC9-PB1-Pad36)") (class "Default")
      (node (ref "IC9") (pin "36") (pinfunction "PB1_36") (pintype "passive"))
    )
    (net (code "96") (name "unconnected-(IC9-PB2-Pad37)") (class "Default")
      (node (ref "IC9") (pin "37") (pinfunction "PB2_37") (pintype "passive"))
    )
    (net (code "97") (name "unconnected-(IC9-PB3-Pad89)") (class "Default")
      (node (ref "IC9") (pin "89") (pinfunction "PB3_89") (pintype "passive"))
    )
    (net (code "98") (name "unconnected-(IC9-PB8-Pad95)") (class "Default")
      (node (ref "IC9") (pin "95") (pinfunction "PB8_95") (pintype "passive"))
    )
    (net (code "99") (name "unconnected-(IC9-PB9-Pad96)") (class "Default")
      (node (ref "IC9") (pin "96") (pinfunction "PB9_96") (pintype "passive"))
    )
    (net (code "100") (name "unconnected-(IC9-PB10-Pad47)") (class "Default")
      (node (ref "IC9") (pin "47") (pinfunction "PB10_47") (pintype "passive"))
    )
    (net (code "101") (name "unconnected-(IC9-PB11-Pad48)") (class "Default")
      (node (ref "IC9") (pin "48") (pinfunction "PB11_48") (pintype "passive"))
    )
    (net (code "102") (name "unconnected-(IC9-PB12-Pad51)") (class "Default")
      (node (ref "IC9") (pin "51") (pinfunction "PB12_51") (pintype "passive"))
    )
    (net (code "103") (name "unconnected-(IC9-PB13-Pad52)") (class "Default")
      (node (ref "IC9") (pin "52") (pinfunction "PB13_52") (pintype "passive"))
    )
    (net (code "104") (name "unconnected-(IC9-PB15-Pad54)") (class "Default")
      (node (ref "IC9") (pin "54") (pinfunction "PB15_54") (pintype "passive"))
    )
    (net (code "105") (name "unconnected-(IC9-PC4-Pad33)") (class "Default")
      (node (ref "IC9") (pin "33") (pinfunction "PC4_33") (pintype "passive"))
    )
    (net (code "106") (name "unconnected-(IC9-PC5-Pad34)") (class "Default")
      (node (ref "IC9") (pin "34") (pinfunction "PC5_34") (pintype "passive"))
    )
    (net (code "107") (name "unconnected-(IC9-PC6-Pad63)") (class "Default")
      (node (ref "IC9") (pin "63") (pinfunction "PC6_63") (pintype "passive"))
    )
    (net (code "108") (name "unconnected-(IC9-PC8-Pad65)") (class "Default")
      (node (ref "IC9") (pin "65") (pinfunction "PC8_65") (pintype "passive"))
    )
    (net (code "109") (name "unconnected-(IC9-PC9-Pad66)") (class "Default")
      (node (ref "IC9") (pin "66") (pinfunction "PC9_66") (pintype "passive"))
    )
    (net (code "110") (name "unconnected-(IC9-PC10-Pad78)") (class "Default")
      (node (ref "IC9") (pin "78") (pinfunction "PC10_78") (pintype "passive"))
    )
    (net (code "111") (name "unconnected-(IC9-PC11-Pad79)") (class "Default")
      (node (ref "IC9") (pin "79") (pinfunction "PC11_79") (pintype "passive"))
    )
    (net (code "112") (name "unconnected-(IC9-PC12-Pad80)") (class "Default")
      (node (ref "IC9") (pin "80") (pinfunction "PC12_80") (pintype "passive"))
    )
    (net (code "113") (name "unconnected-(IC9-PC13-Pad7)") (class "Default")
      (node (ref "IC9") (pin "7") (pinfunction "PC13_7") (pintype "passive"))
    )
    (net (code "114") (name "unconnected-(IC9-PC14-Pad8)") (class "Default")
      (node (ref "IC9") (pin "8") (pinfunction "PC14_8") (pintype "passive"))
    )
    (net (code "115") (name "unconnected-(IC9-PC15-Pad9)") (class "Default")
      (node (ref "IC9") (pin "9") (pinfunction "PC15_9") (pintype "passive"))
    )
    (net (code "116") (name "unconnected-(IC9-PD2-Pad83)") (class "Default")
      (node (ref "IC9") (pin "83") (pinfunction "PD2_83") (pintype "passive"))
    )
    (net (code "117") (name "unconnected-(IC9-PD3-Pad84)") (class "Default")
      (node (ref "IC9") (pin "84") (pinfunction "PD3_84") (pintype "passive"))
    )
    (net (code "118") (name "unconnected-(IC9-PD7-Pad88)") (class "Default")
      (node (ref "IC9") (pin "88") (pinfunction "PD7_88") (pintype "passive"))
    )
    (net (code "119") (name "unconnected-(IC9-PD10-Pad57)") (class "Default")
      (node (ref "IC9") (pin "57") (pinfunction "PD10_57") (pintype "passive"))
    )
    (net (code "120") (name "unconnected-(IC9-PD11-Pad58)") (class "Default")
      (node (ref "IC9") (pin "58") (pinfunction "PD11_58") (pintype "passive"))
    )
    (net (code "121") (name "unconnected-(IC9-PD12-Pad59)") (class "Default")
      (node (ref "IC9") (pin "59") (pinfunction "PD12_59") (pintype "passive"))
    )
    (net (code "122") (name "unconnected-(IC9-PD13-Pad60)") (class "Default")
      (node (ref "IC9") (pin "60") (pinfunction "PD13_60") (pintype "passive"))
    )
    (net (code "123") (name "unconnected-(IC9-PD14-Pad61)") (class "Default")
      (node (ref "IC9") (pin "61") (pinfunction "PD14_61") (pintype "passive"))
    )
    (net (code "124") (name "unconnected-(IC9-PD15-Pad62)") (class "Default")
      (node (ref "IC9") (pin "62") (pinfunction "PD15_62") (pintype "passive"))
    )
    (net (code "125") (name "unconnected-(IC9-PE0-Pad97)") (class "Default")
      (node (ref "IC9") (pin "97") (pinfunction "PE0_97") (pintype "passive"))
    )
    (net (code "126") (name "unconnected-(IC9-PE1-Pad98)") (class "Default")
      (node (ref "IC9") (pin "98") (pinfunction "PE1_98") (pintype "passive"))
    )
    (net (code "127") (name "unconnected-(IC9-PE2-Pad1)") (class "Default")
      (node (ref "IC9") (pin "1") (pinfunction "PE2_1") (pintype "passive"))
    )
    (net (code "128") (name "unconnected-(IC9-PE3-Pad2)") (class "Default")
      (node (ref "IC9") (pin "2") (pinfunction "PE3_2") (pintype "passive"))
    )
    (net (code "129") (name "unconnected-(IC9-PE4-Pad3)") (class "Default")
      (node (ref "IC9") (pin "3") (pinfunction "PE4_3") (pintype "passive"))
    )
    (net (code "130") (name "unconnected-(IC9-PE5-Pad4)") (class "Default")
      (node (ref "IC9") (pin "4") (pinfunction "PE5_4") (pintype "passive"))
    )
    (net (code "131") (name "unconnected-(IC9-PE6-Pad5)") (class "Default")
      (node (ref "IC9") (pin "5") (pinfunction "PE6_5") (pintype "passive"))
    )
    (net (code "132") (name "unconnected-(IC9-PE7-Pad38)") (class "Default")
      (node (ref "IC9") (pin "38") (pinfunction "PE7_38") (pintype "passive"))
    )
    (net (code "133") (name "unconnected-(IC9-PE14-Pad45)") (class "Default")
      (node (ref "IC9") (pin "45") (pinfunction "PE14_45") (pintype "passive"))
    )
    (net (code "134") (name "unconnected-(IC9-PE15-Pad46)") (class "Default")
      (node (ref "IC9") (pin "46") (pinfunction "PE15_46") (pintype "passive"))
    )
    (net (code "135") (name "unconnected-(IC9-PH0-Pad12)") (class "Default")
      (node (ref "IC9") (pin "12") (pinfunction "PH0_12") (pintype "passive"))
    )
    (net (code "136") (name "unconnected-(IC9-PH1-Pad13)") (class "Default")
      (node (ref "IC9") (pin "13") (pinfunction "PH1_13") (pintype "passive"))
    )
    (net (code "137") (name "unconnected-(IC9-VBAT-Pad6)") (class "Default")
      (node (ref "IC9") (pin "6") (pinfunction "VBAT_6") (pintype "passive"))
    )
    (net (code "138") (name "unconnected-(IC9-VCAP_1-Pad49)") (class "Default")
      (node (ref "IC9") (pin "49") (pinfunction "VCAP_1_49") (pintype "passive"))
    )
    (net (code "139") (name "unconnected-(IC9-VCAP_2-Pad73)") (class "Default")
      (node (ref "IC9") (pin "73") (pinfunction "VCAP_2_73") (pintype "passive"))
    )
    (net (code "140") (name "unconnected-(IC9-VDD-Pad19)") (class "Default")
      (node (ref "IC9") (pin "19") (pinfunction "VDD_19") (pintype "passive"))
    )
    (net (code "141") (name "unconnected-(IC9-VREF+-Pad21)") (class "Default")
      (node (ref "IC9") (pin "21") (pinfunction "VREF+_21") (pintype "passive"))
    )
    (net (code "142") (name "unconnected-(IO1A-RS-Pad8)") (class "Default")
      (node (ref "IO1") (pin "8") (pinfunction "RS_8") (pintype "passive"))
    )
    (net (code "143") (name "unconnected-(IO1A-VREF-Pad5)") (class "Default")
      (node (ref "IO1") (pin "5") (pinfunction "VREF_5") (pintype "output"))
    )
    (net (code "144") (name "unconnected-(JP1-Pad3)") (class "Default")
      (node (ref "JP1") (pin "3") (pinfunction "3_3") (pintype "passive"))
    )
    (net (code "145") (name "unconnected-(JP2-Pad1)") (class "Default")
      (node (ref "JP2") (pin "1") (pinfunction "1_1") (pintype "passive"))
    )
    (net (code "146") (name "unconnected-(JP2-Pad2)") (class "Default")
      (node (ref "JP2") (pin "2") (pinfunction "2_2") (pintype "passive"))
    )
    (net (code "147") (name "unconnected-(JP2-Pad3)") (class "Default")
      (node (ref "JP2") (pin "3") (pinfunction "3_3") (pintype "passive"))
    )
    (net (code "148") (name "unconnected-(JP14-Pad1)") (class "Default")
      (node (ref "JP14") (pin "1") (pinfunction "1_1") (pintype "passive"))
    )
    (net (code "149") (name "unconnected-(JP14-Pad2)") (class "Default")
      (node (ref "JP14") (pin "2") (pinfunction "2_2") (pintype "passive"))
    )
    (net (code "150") (name "unconnected-(JP14-Pad3)") (class "Default")
      (node (ref "JP14") (pin "3") (pinfunction "3_3") (pintype "passive"))
    )
    (net (code "151") (name "unconnected-(JP17-Pad3)") (class "Default")
      (node (ref "JP17") (pin "3") (pinfunction "3_3") (pintype "passive"))
    )
    (net (code "152") (name "unconnected-(U$5A-A-Pad6)") (class "Default")
      (node (ref "U$5") (pin "6") (pinfunction "A_6") (pintype "bidirectional"))
    )
    (net (code "153") (name "unconnected-(U$5A-B-Pad7)") (class "Default")
      (node (ref "U$5") (pin "7") (pinfunction "B_7") (pintype "bidirectional"))
    )
  )
)
